# Control_Panel.net
KiCad netlist of a schematic drawn in EAGLE
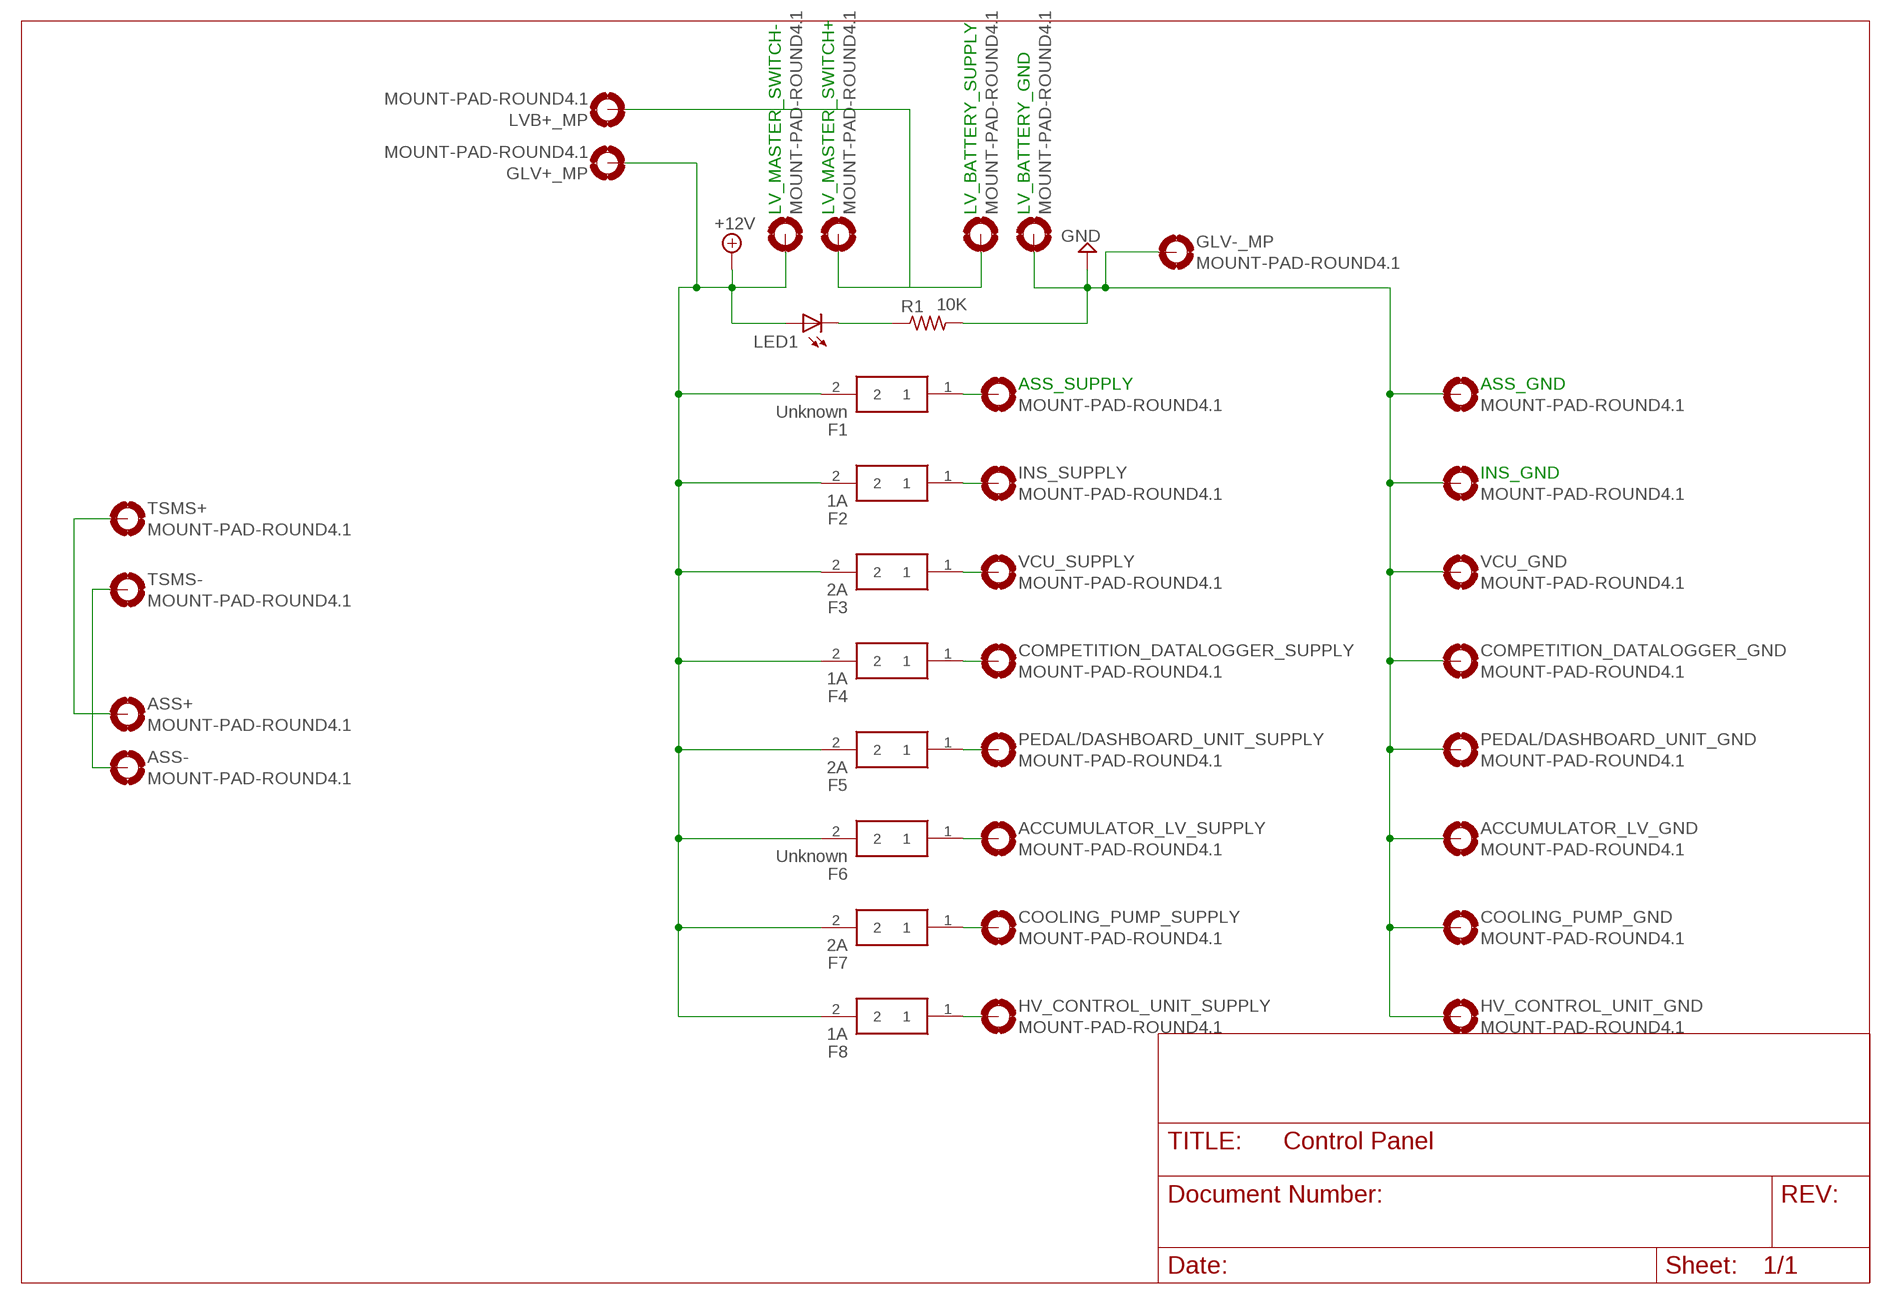
[diagram p0: schematic, sheet 1]

(export (version "E")
  (design (tool "Eeschema 10.0.6"))
  (components
    (comp (ref "ACCUMULATOR_LV_GND")
      (value "MOUNT-PAD-ROUND4.1")
      (footprint "eagle-import:4,1-PAD")
      (libsource (lib "eagle-import") (part "MOUNT-PAD-ROUND4.1"))
    )
    (comp (ref "ACCUMULATOR_LV_SUPPLY")
      (value "MOUNT-PAD-ROUND4.1")
      (footprint "eagle-import:4,1-PAD")
      (libsource (lib "eagle-import") (part "MOUNT-PAD-ROUND4.1"))
    )
    (comp (ref "ASS+")
      (value "MOUNT-PAD-ROUND4.1")
      (footprint "eagle-import:4,1-PAD")
      (libsource (lib "eagle-import") (part "MOUNT-PAD-ROUND4.1"))
    )
    (comp (ref "ASS-")
      (value "MOUNT-PAD-ROUND4.1")
      (footprint "eagle-import:4,1-PAD")
      (libsource (lib "eagle-import") (part "MOUNT-PAD-ROUND4.1"))
    )
    (comp (ref "ASS_GND")
      (value "MOUNT-PAD-ROUND4.1")
      (footprint "eagle-import:4,1-PAD")
      (libsource (lib "eagle-import") (part "MOUNT-PAD-ROUND4.1"))
    )
    (comp (ref "ASS_SUPPLY")
      (value "MOUNT-PAD-ROUND4.1")
      (footprint "eagle-import:4,1-PAD")
      (libsource (lib "eagle-import") (part "MOUNT-PAD-ROUND4.1"))
    )
    (comp (ref "COMPETITION_DATALOGGER_GND")
      (value "MOUNT-PAD-ROUND4.1")
      (footprint "eagle-import:4,1-PAD")
      (libsource (lib "eagle-import") (part "MOUNT-PAD-ROUND4.1"))
    )
    (comp (ref "COMPETITION_DATALOGGER_SUPPLY")
      (value "MOUNT-PAD-ROUND4.1")
      (footprint "eagle-import:4,1-PAD")
      (libsource (lib "eagle-import") (part "MOUNT-PAD-ROUND4.1"))
    )
    (comp (ref "COOLING_PUMP_GND")
      (value "MOUNT-PAD-ROUND4.1")
      (footprint "eagle-import:4,1-PAD")
      (libsource (lib "eagle-import") (part "MOUNT-PAD-ROUND4.1"))
    )
    (comp (ref "COOLING_PUMP_SUPPLY")
      (value "MOUNT-PAD-ROUND4.1")
      (footprint "eagle-import:4,1-PAD")
      (libsource (lib "eagle-import") (part "MOUNT-PAD-ROUND4.1"))
    )
    (comp (ref "F1")
      (value "Unknown")
      (footprint "eagle-import:01530008")
      (fields (field (name "MANUFACTURER_PART_NUMBER") "01530008Z") (field (name "RS_PART_NUMBER") "3607317"))
      (libsource (lib "eagle-import") (part "01530008Z"))
    )
    (comp (ref "F2")
      (value "1A")
      (footprint "eagle-import:01530008")
      (fields (field (name "MANUFACTURER_PART_NUMBER") "01530008Z") (field (name "RS_PART_NUMBER") "3607317"))
      (libsource (lib "eagle-import") (part "01530008Z"))
    )
    (comp (ref "F3")
      (value "2A")
      (footprint "eagle-import:01530008")
      (fields (field (name "MANUFACTURER_PART_NUMBER") "01530008Z") (field (name "RS_PART_NUMBER") "3607317"))
      (libsource (lib "eagle-import") (part "01530008Z"))
    )
    (comp (ref "F4")
      (value "1A")
      (footprint "eagle-import:01530008")
      (fields (field (name "MANUFACTURER_PART_NUMBER") "01530008Z") (field (name "RS_PART_NUMBER") "3607317"))
      (libsource (lib "eagle-import") (part "01530008Z"))
    )
    (comp (ref "F5")
      (value "2A")
      (footprint "eagle-import:01530008")
      (fields (field (name "MANUFACTURER_PART_NUMBER") "01530008Z") (field (name "RS_PART_NUMBER") "3607317"))
      (libsource (lib "eagle-import") (part "01530008Z"))
    )
    (comp (ref "F6")
      (value "Unknown")
      (footprint "eagle-import:01530008")
      (fields (field (name "MANUFACTURER_PART_NUMBER") "01530008Z") (field (name "RS_PART_NUMBER") "3607317"))
      (libsource (lib "eagle-import") (part "01530008Z"))
    )
    (comp (ref "F7")
      (value "2A")
      (footprint "eagle-import:01530008")
      (fields (field (name "MANUFACTURER_PART_NUMBER") "01530008Z") (field (name "RS_PART_NUMBER") "3607317"))
      (libsource (lib "eagle-import") (part "01530008Z"))
    )
    (comp (ref "F8")
      (value "1A")
      (footprint "eagle-import:01530008")
      (fields (field (name "MANUFACTURER_PART_NUMBER") "01530008Z") (field (name "RS_PART_NUMBER") "3607317"))
      (libsource (lib "eagle-import") (part "01530008Z"))
    )
    (comp (ref "GLV+_MP")
      (value "MOUNT-PAD-ROUND4.1")
      (footprint "eagle-import:4,1-PAD")
      (libsource (lib "eagle-import") (part "MOUNT-PAD-ROUND4.1"))
    )
    (comp (ref "GLV-_MP")
      (value "MOUNT-PAD-ROUND4.1")
      (footprint "eagle-import:4,1-PAD")
      (libsource (lib "eagle-import") (part "MOUNT-PAD-ROUND4.1"))
    )
    (comp (ref "HV_CONTROL_UNIT_GND")
      (value "MOUNT-PAD-ROUND4.1")
      (footprint "eagle-import:4,1-PAD")
      (libsource (lib "eagle-import") (part "MOUNT-PAD-ROUND4.1"))
    )
    (comp (ref "HV_CONTROL_UNIT_SUPPLY")
      (value "MOUNT-PAD-ROUND4.1")
      (footprint "eagle-import:4,1-PAD")
      (libsource (lib "eagle-import") (part "MOUNT-PAD-ROUND4.1"))
    )
    (comp (ref "INS_GND")
      (value "MOUNT-PAD-ROUND4.1")
      (footprint "eagle-import:4,1-PAD")
      (libsource (lib "eagle-import") (part "MOUNT-PAD-ROUND4.1"))
    )
    (comp (ref "INS_SUPPLY")
      (value "MOUNT-PAD-ROUND4.1")
      (footprint "eagle-import:4,1-PAD")
      (libsource (lib "eagle-import") (part "MOUNT-PAD-ROUND4.1"))
    )
    (comp (ref "LED1")
      (value "LED3MM")
      (footprint "eagle-import:LED3MM")
      (libsource (lib "eagle-import") (part "LED3MM"))
    )
    (comp (ref "LVB+_MP")
      (value "MOUNT-PAD-ROUND4.1")
      (footprint "eagle-import:4,1-PAD")
      (libsource (lib "eagle-import") (part "MOUNT-PAD-ROUND4.1"))
    )
    (comp (ref "LV_BATTERY_GND")
      (value "MOUNT-PAD-ROUND4.1")
      (footprint "eagle-import:4,1-PAD")
      (libsource (lib "eagle-import") (part "MOUNT-PAD-ROUND4.1"))
    )
    (comp (ref "LV_BATTERY_SUPPLY")
      (value "MOUNT-PAD-ROUND4.1")
      (footprint "eagle-import:4,1-PAD")
      (libsource (lib "eagle-import") (part "MOUNT-PAD-ROUND4.1"))
    )
    (comp (ref "LV_MASTER_SWITCH+")
      (value "MOUNT-PAD-ROUND4.1")
      (footprint "eagle-import:4,1-PAD")
      (libsource (lib "eagle-import") (part "MOUNT-PAD-ROUND4.1"))
    )
    (comp (ref "LV_MASTER_SWITCH-")
      (value "MOUNT-PAD-ROUND4.1")
      (footprint "eagle-import:4,1-PAD")
      (libsource (lib "eagle-import") (part "MOUNT-PAD-ROUND4.1"))
    )
    (comp (ref "PEDAL/DASHBOARD_UNIT_GND")
      (value "MOUNT-PAD-ROUND4.1")
      (footprint "eagle-import:4,1-PAD")
      (libsource (lib "eagle-import") (part "MOUNT-PAD-ROUND4.1"))
    )
    (comp (ref "PEDAL/DASHBOARD_UNIT_SUPPLY")
      (value "MOUNT-PAD-ROUND4.1")
      (footprint "eagle-import:4,1-PAD")
      (libsource (lib "eagle-import") (part "MOUNT-PAD-ROUND4.1"))
    )
    (comp (ref "R1")
      (value "10K")
      (footprint "eagle-import:0207_12")
      (libsource (lib "eagle-import") (part "R-US_0207/12"))
    )
    (comp (ref "TSMS+")
      (value "MOUNT-PAD-ROUND4.1")
      (footprint "eagle-import:4,1-PAD")
      (libsource (lib "eagle-import") (part "MOUNT-PAD-ROUND4.1"))
    )
    (comp (ref "TSMS-")
      (value "MOUNT-PAD-ROUND4.1")
      (footprint "eagle-import:4,1-PAD")
      (libsource (lib "eagle-import") (part "MOUNT-PAD-ROUND4.1"))
    )
    (comp (ref "VCU_GND")
      (value "MOUNT-PAD-ROUND4.1")
      (footprint "eagle-import:4,1-PAD")
      (libsource (lib "eagle-import") (part "MOUNT-PAD-ROUND4.1"))
    )
    (comp (ref "VCU_SUPPLY")
      (value "MOUNT-PAD-ROUND4.1")
      (footprint "eagle-import:4,1-PAD")
      (libsource (lib "eagle-import") (part "MOUNT-PAD-ROUND4.1"))
    )
  )
  (nets
    (net (code "1") (name "+12V") (class "Default")
      (node (ref "F1") (pin "2") (pinfunction "2_2") (pintype "bidirectional"))
      (node (ref "F2") (pin "2") (pinfunction "2_2") (pintype "bidirectional"))
      (node (ref "F3") (pin "2") (pinfunction "2_2") (pintype "bidirectional"))
      (node (ref "F4") (pin "2") (pinfunction "2_2") (pintype "bidirectional"))
      (node (ref "F5") (pin "2") (pinfunction "2_2") (pintype "bidirectional"))
      (node (ref "F6") (pin "2") (pinfunction "2_2") (pintype "bidirectional"))
      (node (ref "F7") (pin "2") (pinfunction "2_2") (pintype "bidirectional"))
      (node (ref "F8") (pin "2") (pinfunction "2_2") (pintype "bidirectional"))
      (node (ref "GLV+_MP") (pin "B4,1") (pinfunction "MOUNT_B4,1") (pintype "passive"))
      (node (ref "LED1") (pin "A") (pinfunction "A_A") (pintype "passive"))
      (node (ref "LV_MASTER_SWITCH-") (pin "B4,1") (pinfunction "MOUNT_B4,1") (pintype "passive"))
    )
    (net (code "2") (name "GND") (class "Default")
      (node (ref "ACCUMULATOR_LV_GND") (pin "B4,1") (pinfunction "MOUNT_B4,1") (pintype "passive"))
      (node (ref "ASS_GND") (pin "B4,1") (pinfunction "MOUNT_B4,1") (pintype "passive"))
      (node (ref "COMPETITION_DATALOGGER_GND") (pin "B4,1") (pinfunction "MOUNT_B4,1") (pintype "passive"))
      (node (ref "COOLING_PUMP_GND") (pin "B4,1") (pinfunction "MOUNT_B4,1") (pintype "passive"))
      (node (ref "GLV-_MP") (pin "B4,1") (pinfunction "MOUNT_B4,1") (pintype "passive"))
      (node (ref "HV_CONTROL_UNIT_GND") (pin "B4,1") (pinfunction "MOUNT_B4,1") (pintype "passive"))
      (node (ref "INS_GND") (pin "B4,1") (pinfunction "MOUNT_B4,1") (pintype "passive"))
      (node (ref "LV_BATTERY_GND") (pin "B4,1") (pinfunction "MOUNT_B4,1") (pintype "passive"))
      (node (ref "PEDAL/DASHBOARD_UNIT_GND") (pin "B4,1") (pinfunction "MOUNT_B4,1") (pintype "passive"))
      (node (ref "R1") (pin "2") (pinfunction "2_2") (pintype "passive"))
      (node (ref "VCU_GND") (pin "B4,1") (pinfunction "MOUNT_B4,1") (pintype "passive"))
    )
    (net (code "3") (name "Net-(ACCUMULATOR_LV_SUPPLY-MOUNT)") (class "Default")
      (node (ref "ACCUMULATOR_LV_SUPPLY") (pin "B4,1") (pinfunction "MOUNT_B4,1") (pintype "passive"))
      (node (ref "F6") (pin "1") (pinfunction "1_1") (pintype "bidirectional"))
    )
    (net (code "4") (name "Net-(ASS+-MOUNT)") (class "Default")
      (node (ref "ASS+") (pin "B4,1") (pinfunction "MOUNT_B4,1") (pintype "passive"))
      (node (ref "TSMS+") (pin "B4,1") (pinfunction "MOUNT_B4,1") (pintype "passive"))
    )
    (net (code "5") (name "Net-(ASS--MOUNT)") (class "Default")
      (node (ref "ASS-") (pin "B4,1") (pinfunction "MOUNT_B4,1") (pintype "passive"))
      (node (ref "TSMS-") (pin "B4,1") (pinfunction "MOUNT_B4,1") (pintype "passive"))
    )
    (net (code "6") (name "Net-(ASS_SUPPLY-MOUNT)") (class "Default")
      (node (ref "ASS_SUPPLY") (pin "B4,1") (pinfunction "MOUNT_B4,1") (pintype "passive"))
      (node (ref "F1") (pin "1") (pinfunction "1_1") (pintype "bidirectional"))
    )
    (net (code "7") (name "Net-(COMPETITION_DATALOGGER_SUPPLY-MOUNT)") (class "Default")
      (node (ref "COMPETITION_DATALOGGER_SUPPLY") (pin "B4,1") (pinfunction "MOUNT_B4,1") (pintype "passive"))
      (node (ref "F4") (pin "1") (pinfunction "1_1") (pintype "bidirectional"))
    )
    (net (code "8") (name "Net-(COOLING_PUMP_SUPPLY-MOUNT)") (class "Default")
      (node (ref "COOLING_PUMP_SUPPLY") (pin "B4,1") (pinfunction "MOUNT_B4,1") (pintype "passive"))
      (node (ref "F7") (pin "1") (pinfunction "1_1") (pintype "bidirectional"))
    )
    (net (code "9") (name "Net-(HV_CONTROL_UNIT_SUPPLY-MOUNT)") (class "Default")
      (node (ref "F8") (pin "1") (pinfunction "1_1") (pintype "bidirectional"))
      (node (ref "HV_CONTROL_UNIT_SUPPLY") (pin "B4,1") (pinfunction "MOUNT_B4,1") (pintype "passive"))
    )
    (net (code "10") (name "Net-(INS_SUPPLY-MOUNT)") (class "Default")
      (node (ref "F2") (pin "1") (pinfunction "1_1") (pintype "bidirectional"))
      (node (ref "INS_SUPPLY") (pin "B4,1") (pinfunction "MOUNT_B4,1") (pintype "passive"))
    )
    (net (code "11") (name "Net-(LED1-C)") (class "Default")
      (node (ref "LED1") (pin "K") (pinfunction "C_K") (pintype "passive"))
      (node (ref "R1") (pin "1") (pinfunction "1_1") (pintype "passive"))
    )
    (net (code "12") (name "Net-(LVB+_MP-MOUNT)") (class "Default")
      (node (ref "LVB+_MP") (pin "B4,1") (pinfunction "MOUNT_B4,1") (pintype "passive"))
      (node (ref "LV_BATTERY_SUPPLY") (pin "B4,1") (pinfunction "MOUNT_B4,1") (pintype "passive"))
      (node (ref "LV_MASTER_SWITCH+") (pin "B4,1") (pinfunction "MOUNT_B4,1") (pintype "passive"))
    )
    (net (code "13") (name "Net-(PEDAL/DASHBOARD_UNIT_SUPPLY-MOUNT)") (class "Default")
      (node (ref "F5") (pin "1") (pinfunction "1_1") (pintype "bidirectional"))
      (node (ref "PEDAL/DASHBOARD_UNIT_SUPPLY") (pin "B4,1") (pinfunction "MOUNT_B4,1") (pintype "passive"))
    )
    (net (code "14") (name "Net-(VCU_SUPPLY-MOUNT)") (class "Default")
      (node (ref "F3") (pin "1") (pinfunction "1_1") (pintype "bidirectional"))
      (node (ref "VCU_SUPPLY") (pin "B4,1") (pinfunction "MOUNT_B4,1") (pintype "passive"))
    )
  )
)
